# Power.net
KiCad netlist of a schematic drawn in Altium Designer
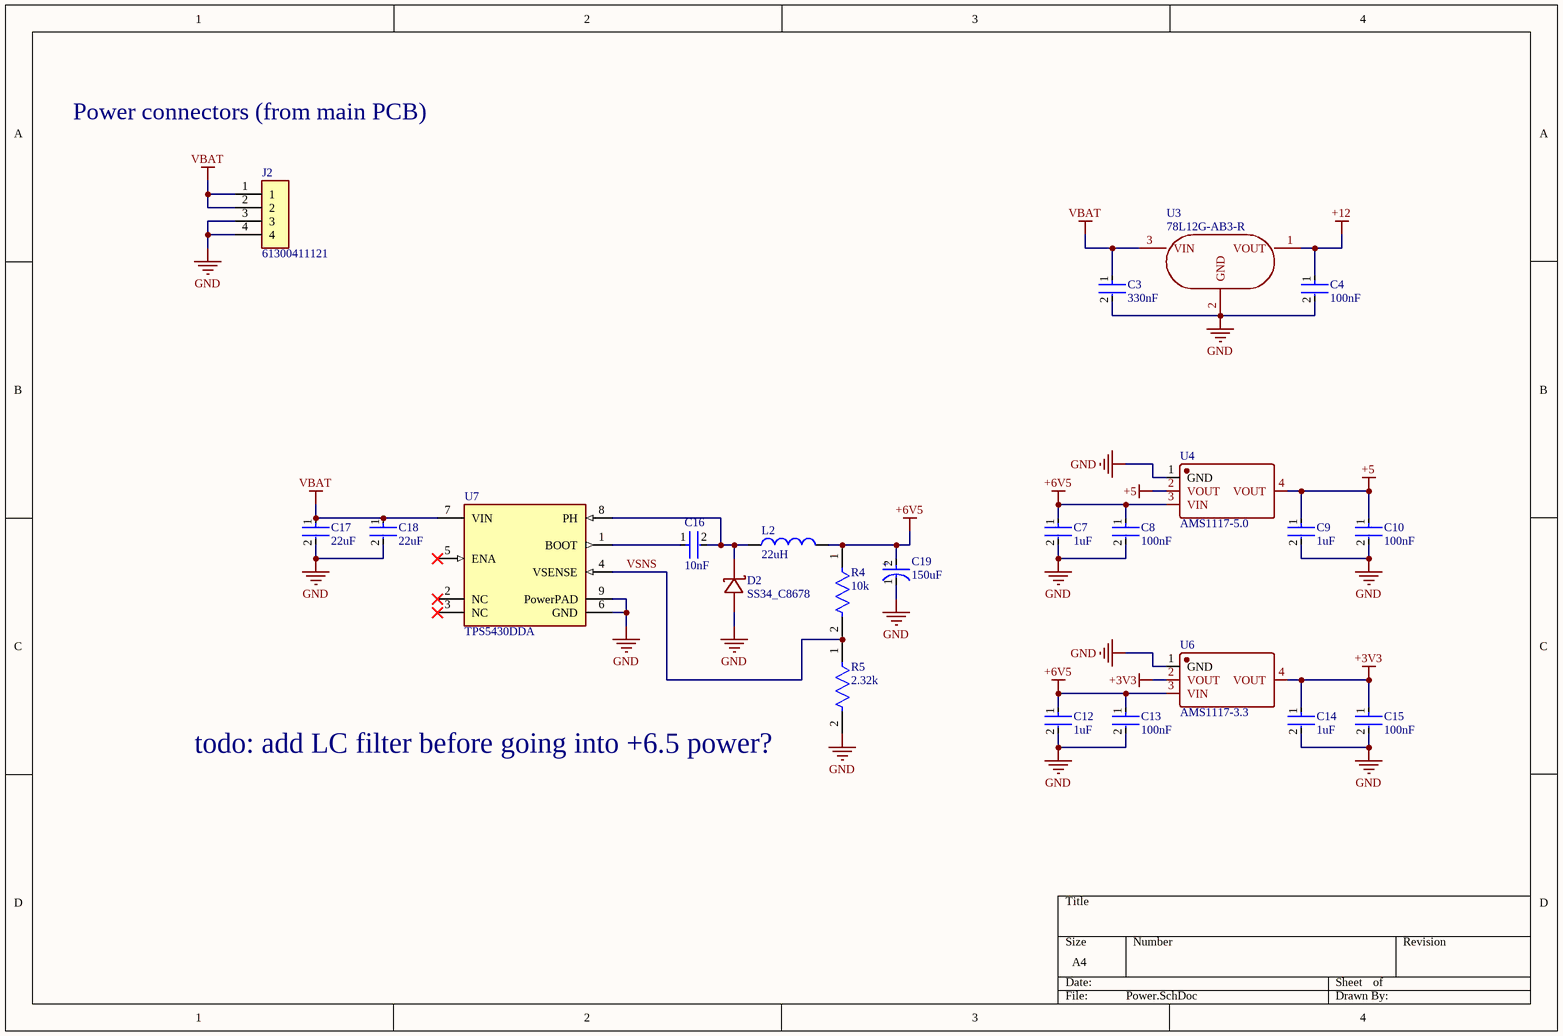
[diagram p0: Power.SchDoc]

(export (version "E")
  (design (tool "Eeschema 10.0.6"))
  (components
    (comp (ref "C3")
      (value "330nF")
      (footprint "FP-GCM188-0_1-IPC_A")
      (description "50V 330nF X7R ±10% 0603 Multilayer Ceramic Capacitors MLCC - SMD/SMT ROHS")
      (libsource (lib "Hornet X Elec") (part "02cd4be3c70576c341d710602a673aa"))
    )
    (comp (ref "C4")
      (value "100nF")
      (footprint "FP-GCM188-0_1-IPC_A")
      (libsource (lib "Hornet X Elec") (part "02cd4be3c70576c341d710602a673aa"))
    )
    (comp (ref "C7")
      (value "1uF")
      (footprint "FP-CC0805-0_85-IPC_A")
      (libsource (lib "Hornet X Elec") (part "11868f565c42a9108669ba33697ecf6"))
    )
    (comp (ref "C8")
      (value "100nF")
      (footprint "FP-GCM188-0_1-IPC_A")
      (libsource (lib "Hornet X Elec") (part "02cd4be3c70576c341d710602a673aa"))
    )
    (comp (ref "C9")
      (value "1uF")
      (footprint "FP-CC0805-0_85-IPC_A")
      (libsource (lib "Hornet X Elec") (part "11868f565c42a9108669ba33697ecf6"))
    )
    (comp (ref "C10")
      (value "100nF")
      (footprint "FP-GCM188-0_1-IPC_A")
      (libsource (lib "Hornet X Elec") (part "02cd4be3c70576c341d710602a673aa"))
    )
    (comp (ref "C12")
      (value "1uF")
      (footprint "FP-CC0805-0_85-IPC_A")
      (libsource (lib "Hornet X Elec") (part "11868f565c42a9108669ba33697ecf6"))
    )
    (comp (ref "C13")
      (value "100nF")
      (footprint "FP-GCM188-0_1-IPC_A")
      (libsource (lib "Hornet X Elec") (part "02cd4be3c70576c341d710602a673aa"))
    )
    (comp (ref "C14")
      (value "1uF")
      (footprint "FP-CC0805-0_85-IPC_A")
      (libsource (lib "Hornet X Elec") (part "11868f565c42a9108669ba33697ecf6"))
    )
    (comp (ref "C15")
      (value "100nF")
      (footprint "FP-GCM188-0_1-IPC_A")
      (libsource (lib "Hornet X Elec") (part "02cd4be3c70576c341d710602a673aa"))
    )
    (comp (ref "C16")
      (value "10nF")
      (footprint "FP-GCM188-0_1-IPC_A")
      (description "50V 10nF ceramic 0603 capacitor")
      (libsource (lib "Hornet X Elec") (part "02cd4be3c70576c341d710602a673aa"))
    )
    (comp (ref "C17")
      (value "22uF")
      (footprint "FP-CC0805-0_85-IPC_A")
      (description "35V 22uF X5R 卤20% 0805 Multilayer Ceramic Capacitors MLCC - SMD/SMT ROHS")
      (libsource (lib "Hornet X Elec") (part "02cd4be3c70576c341d710602a673aa"))
    )
    (comp (ref "C18")
      (value "22uF")
      (footprint "FP-CC0805-0_85-IPC_A")
      (description "35V 22uF X5R 卤20% 0805 Multilayer Ceramic Capacitors MLCC - SMD/SMT ROHS")
      (libsource (lib "Hornet X Elec") (part "02cd4be3c70576c341d710602a673aa"))
    )
    (comp (ref "C19")
      (value "150uF")
      (footprint "FP-POSCAP-D3L-MFG")
      (libsource (lib "Hornet X Elec") (part "a00bbbee19879c290e62620ae7e47b1"))
    )
    (comp (ref "D2")
      (value "SS34_C8678")
      (footprint "SS34_C8678-Footprint-1")
      (description "SS34 40V 3A Schottky Diode")
      (libsource (lib "Hornet X Elec") (part "New symbol 1"))
    )
    (comp (ref "J2")
      (value "61300411121")
      (footprint "61300411121-Footprint-1")
      (description "4P Single Row 2.54mm Wurth Elektronik Header Pin (inverted 3D model)")
      (libsource (lib "Hornet X Elec") (part "61300411121-Symbol-1"))
    )
    (comp (ref "L2")
      (value "22uH")
      (footprint "INDP7066X28N")
      (description "2.5A 22uH Integrated molded inductor ±20% 3A SMD,6.6x7mm Power Inductors ROHS")
      (libsource (lib "Hornet X Elec") (part "IND-2"))
    )
    (comp (ref "R4")
      (value "10k")
      (footprint "FP-RT0603-IPC_A")
      (fields (field (name "POWER") "100mW") (field (name "TOLERANCE") "1%"))
      (libsource (lib "Hornet X Elec") (part "1029c3af85768c4190bb7ad29bc67b5"))
    )
    (comp (ref "R5")
      (value "2.32k")
      (footprint "FP-RT0603-IPC_A")
      (fields (field (name "POWER") "100mW") (field (name "TOLERANCE") "1%"))
      (libsource (lib "Hornet X Elec") (part "1029c3af85768c4190bb7ad29bc67b5"))
    )
    (comp (ref "U3")
      (value "78L12G-AB3-R")
      (footprint "78L12G-AB3-R-Footprint-1")
      (description "12V 100mA LDO Regulator")
      (libsource (lib "Hornet X Elec") (part "78L12G-AB3-R-Symbol-1"))
    )
    (comp (ref "U4")
      (value "AMS1117-5.0")
      (footprint "AMS1117-5.0-Footprint-1")
      (description "5V Reg")
      (libsource (lib "Hornet X Elec") (part "AMS1117-5.0-Symbol-1"))
    )
    (comp (ref "U6")
      (value "AMS1117-3.3")
      (footprint "AMS1117-5.0-Footprint-1")
      (description "3.3V Reg")
      (libsource (lib "Hornet X Elec") (part "AMS1117-5.0-Symbol-1"))
    )
    (comp (ref "U7")
      (value "TPS5430DDA")
      (footprint "FP-DDA0008J-MFG")
      (description "Switching Regulator, Voltage-mode, 6A, 500kHz Switching Freq-Max, PDSO8")
      (libsource (lib "Hornet X Elec") (part "98da629940cea6febc5630bb55159f3"))
    )
  )
  (nets
    (net (code "1") (name "+3V3") (class "Default")
      (node (ref "C14") (pin "1") (pinfunction "1_1") (pintype "passive"))
      (node (ref "C15") (pin "1") (pinfunction "1_1") (pintype "passive"))
      (node (ref "U6") (pin "2") (pinfunction "VOUT_2") (pintype "passive"))
      (node (ref "U6") (pin "4") (pinfunction "VOUT_4") (pintype "passive"))
    )
    (net (code "2") (name "+5") (class "Default")
      (node (ref "C10") (pin "1") (pinfunction "1_1") (pintype "passive"))
      (node (ref "C9") (pin "1") (pinfunction "1_1") (pintype "passive"))
      (node (ref "U4") (pin "2") (pinfunction "VOUT_2") (pintype "passive"))
      (node (ref "U4") (pin "4") (pinfunction "VOUT_4") (pintype "passive"))
    )
    (net (code "3") (name "+6V5") (class "Default")
      (node (ref "C12") (pin "1") (pinfunction "1_1") (pintype "passive"))
      (node (ref "C13") (pin "1") (pinfunction "1_1") (pintype "passive"))
      (node (ref "C19") (pin "2") (pinfunction "A_2") (pintype "passive"))
      (node (ref "C7") (pin "1") (pinfunction "1_1") (pintype "passive"))
      (node (ref "C8") (pin "1") (pinfunction "1_1") (pintype "passive"))
      (node (ref "L2") (pin "2") (pinfunction "2_2") (pintype "passive"))
      (node (ref "R4") (pin "1") (pinfunction "1_1") (pintype "passive"))
      (node (ref "U4") (pin "3") (pinfunction "VIN_3") (pintype "passive"))
      (node (ref "U6") (pin "3") (pinfunction "VIN_3") (pintype "passive"))
    )
    (net (code "4") (name "+12") (class "Default")
      (node (ref "C4") (pin "1") (pinfunction "1_1") (pintype "passive"))
      (node (ref "U3") (pin "1") (pinfunction "VOUT_1") (pintype "passive"))
    )
    (net (code "5") (name "/VSNS") (class "Default")
      (node (ref "R4") (pin "2") (pinfunction "2_2") (pintype "passive"))
      (node (ref "R5") (pin "1") (pinfunction "1_1") (pintype "passive"))
      (node (ref "U7") (pin "4") (pinfunction "VSENSE_4") (pintype "input"))
    )
    (net (code "6") (name "GND") (class "Default")
      (node (ref "C10") (pin "2") (pinfunction "2_2") (pintype "passive"))
      (node (ref "C12") (pin "2") (pinfunction "2_2") (pintype "passive"))
      (node (ref "C13") (pin "2") (pinfunction "2_2") (pintype "passive"))
      (node (ref "C14") (pin "2") (pinfunction "2_2") (pintype "passive"))
      (node (ref "C15") (pin "2") (pinfunction "2_2") (pintype "passive"))
      (node (ref "C17") (pin "2") (pinfunction "2_2") (pintype "passive"))
      (node (ref "C18") (pin "2") (pinfunction "2_2") (pintype "passive"))
      (node (ref "C19") (pin "1") (pinfunction "C_1") (pintype "passive"))
      (node (ref "C3") (pin "2") (pinfunction "2_2") (pintype "passive"))
      (node (ref "C4") (pin "2") (pinfunction "2_2") (pintype "passive"))
      (node (ref "C7") (pin "2") (pinfunction "2_2") (pintype "passive"))
      (node (ref "C8") (pin "2") (pinfunction "2_2") (pintype "passive"))
      (node (ref "C9") (pin "2") (pinfunction "2_2") (pintype "passive"))
      (node (ref "D2") (pin "2") (pinfunction "A_2") (pintype "passive"))
      (node (ref "J2") (pin "3") (pinfunction "3_3") (pintype "passive"))
      (node (ref "J2") (pin "4") (pinfunction "4_4") (pintype "passive"))
      (node (ref "R5") (pin "2") (pinfunction "2_2") (pintype "passive"))
      (node (ref "U3") (pin "2") (pinfunction "GND_2") (pintype "passive"))
      (node (ref "U4") (pin "1") (pinfunction "GND_1") (pintype "passive"))
      (node (ref "U6") (pin "1") (pinfunction "GND_1") (pintype "passive"))
      (node (ref "U7") (pin "6") (pinfunction "GND_6") (pintype "power_in"))
      (node (ref "U7") (pin "9") (pinfunction "PowerPAD_9") (pintype "power_in"))
    )
    (net (code "7") (name "Net-(D2-K)") (class "Default")
      (node (ref "C16") (pin "2") (pinfunction "2_2") (pintype "passive"))
      (node (ref "D2") (pin "1") (pinfunction "K_1") (pintype "passive"))
      (node (ref "L2") (pin "1") (pinfunction "1_1") (pintype "passive"))
      (node (ref "U7") (pin "8") (pinfunction "PH_8") (pintype "input"))
    )
    (net (code "8") (name "Net-(U7-BOOT)") (class "Default")
      (node (ref "C16") (pin "1") (pinfunction "1_1") (pintype "passive"))
      (node (ref "U7") (pin "1") (pinfunction "BOOT_1") (pintype "output"))
    )
    (net (code "9") (name "VBAT") (class "Default")
      (node (ref "C17") (pin "1") (pinfunction "1_1") (pintype "passive"))
      (node (ref "C18") (pin "1") (pinfunction "1_1") (pintype "passive"))
      (node (ref "C3") (pin "1") (pinfunction "1_1") (pintype "passive"))
      (node (ref "J2") (pin "1") (pinfunction "1_1") (pintype "passive"))
      (node (ref "J2") (pin "2") (pinfunction "2_2") (pintype "passive"))
      (node (ref "U3") (pin "3") (pinfunction "VIN_3") (pintype "passive"))
      (node (ref "U7") (pin "7") (pinfunction "VIN_7") (pintype "power_in"))
    )
    (net (code "10") (name "unconnected-(U7-ENA-Pad5)") (class "Default")
      (node (ref "U7") (pin "5") (pinfunction "ENA_5") (pintype "input+no_connect"))
    )
    (net (code "11") (name "unconnected-(U7-NC-Pad2)") (class "Default")
      (node (ref "U7") (pin "2") (pinfunction "NC_2") (pintype "passive+no_connect"))
    )
    (net (code "12") (name "unconnected-(U7-NC-Pad3)") (class "Default")
      (node (ref "U7") (pin "3") (pinfunction "NC_3") (pintype "passive+no_connect"))
    )
  )
)
